# 3V8_Buck_Boost_Converter.net
KiCad netlist of a schematic drawn in Altium Designer
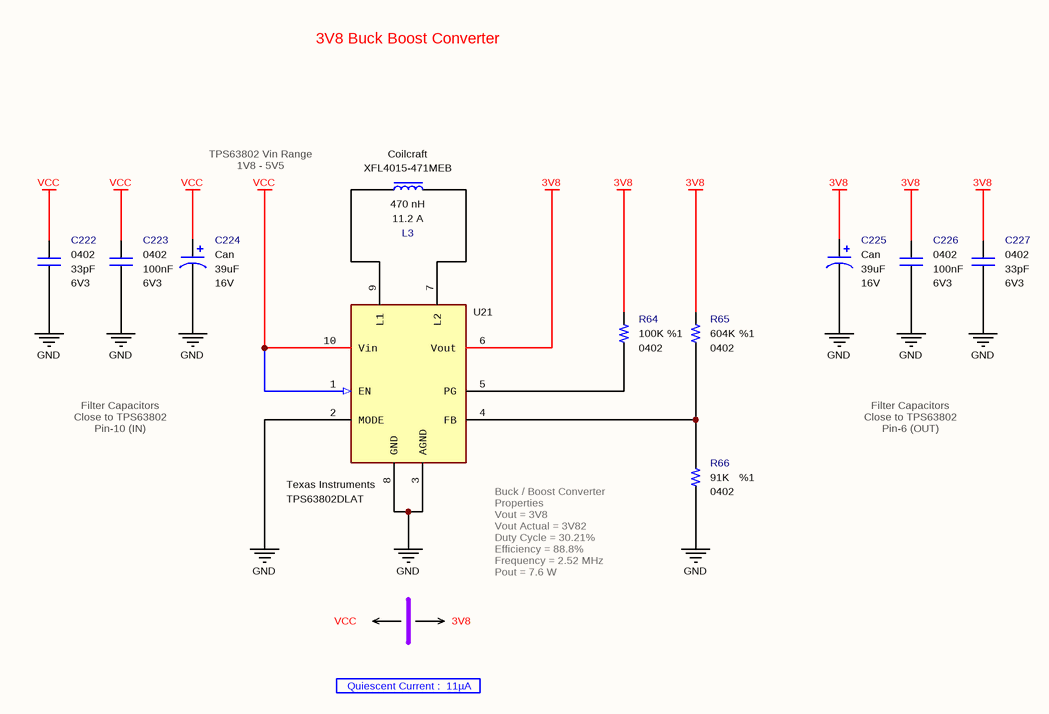
[diagram p0: 3V8 Buck Boost Converter.SchDoc]

(export (version "E")
  (design (tool "Eeschema 10.0.6"))
  (components
    (comp (ref "C222")
      (value "33pF")
      (footprint "CAPACITOR_0402")
      (description "Capacitor - 33pF [0402] (Ceramic)")
      (fields
        (field (name "TOLERANCE") "10%")
        (field (name "CASE") "0402")
        (field (name "VOLTAGE") "6V3")
        (field (name "MANUFACTURER PART NUMBER") "C0402C330J9RACAUTO")
      )
      (libsource (lib "Ovoo_Library") (part "Capacitor - 33pF [0402-6V3]"))
    )
    (comp (ref "C223")
      (value "100nF")
      (footprint "CAPACITOR_0402")
      (description "Capacitor - 100nF [0402-6V3] (Ceramic)")
      (fields
        (field (name "CASE") "0402")
        (field (name "TOLERANCE") "%10")
        (field (name "VOLTAGE") "6V3")
        (field (name "MANUFACTURER PART NUMBER") "04026D104KAT4A")
      )
      (libsource (lib "Ovoo_Library") (part "Capacitor - 100nF [0402-6V3]"))
    )
    (comp (ref "C224")
      (value "39uF")
      (footprint "CAPACITOR_CAN-B6")
      (description "Capacitor - 39uF 16V [Can] (Electrolytic)")
      (fields
        (field (name "TOLERANCE") "20%")
        (field (name "CASE") "Can")
        (field (name "VOLTAGE") "16V")
        (field (name "MANUFACTURER PART NUMBER") "16SVPC39MV")
      )
      (libsource (lib "Ovoo_Library") (part "Capacitor - 39uF [Can-16V]"))
    )
    (comp (ref "C225")
      (value "39uF")
      (footprint "CAPACITOR_CAN-B6")
      (description "Capacitor - 39uF 16V [Can] (Electrolytic)")
      (fields
        (field (name "TOLERANCE") "20%")
        (field (name "CASE") "Can")
        (field (name "VOLTAGE") "16V")
        (field (name "MANUFACTURER PART NUMBER") "16SVPC39MV")
      )
      (libsource (lib "Ovoo_Library") (part "Capacitor - 39uF [Can-16V]"))
    )
    (comp (ref "C226")
      (value "100nF")
      (footprint "CAPACITOR_0402")
      (description "Capacitor - 100nF [0402-6V3] (Ceramic)")
      (fields
        (field (name "CASE") "0402")
        (field (name "TOLERANCE") "%10")
        (field (name "VOLTAGE") "6V3")
        (field (name "MANUFACTURER PART NUMBER") "04026D104KAT4A")
      )
      (libsource (lib "Ovoo_Library") (part "Capacitor - 100nF [0402-6V3]"))
    )
    (comp (ref "C227")
      (value "33pF")
      (footprint "CAPACITOR_0402")
      (description "Capacitor - 33pF [0402] (Ceramic)")
      (fields
        (field (name "TOLERANCE") "10%")
        (field (name "CASE") "0402")
        (field (name "VOLTAGE") "6V3")
        (field (name "MANUFACTURER PART NUMBER") "C0402C330J9RACAUTO")
      )
      (libsource (lib "Ovoo_Library") (part "Capacitor - 33pF [0402-6V3]"))
    )
    (comp (ref "L3")
      (value "470 nH")
      (footprint "INDUCTOR_XFL4015")
      (description "Fixed Inductors 0.47uH 20% 11.2A 8.36mOhms AEC-Q200")
      (fields
        (field (name "TOLERANCE") "20%")
        (field (name "MAXIMUM DC CURRENT") "11.2 A")
        (field (name "MOUSER PART NUMBER") "994-XFL4015-471MEB")
        (field (name "MANUFACTURER PART NUMBER") "XFL4015-471MEB")
        (field (name "MANUFACTURER NAME") "Coilcraft")
      )
      (libsource (lib "Ovoo_Library") (part "Inductor - 470 nH [SMD]"))
    )
    (comp (ref "R64")
      (value "100K")
      (footprint "RESISTOR_0402")
      (description "Thick Film Resistors - SMD 1/16 W 100 Kohms 1%")
      (fields
        (field (name "TOLERANCE") "%1")
        (field (name "CASE") "0402")
        (field (name "MANUFACTURER PART NUMBER") "CRCW0402100KFKED")
        (field (name "MOUSER PART NUMBER") "71-CRCW0402-100K-E3")
      )
      (libsource (lib "Ovoo_Library") (part "Resistor - 100K"))
    )
    (comp (ref "R65")
      (value "604K")
      (footprint "RESISTOR_0402")
      (description "Thick Film Resistors - SMD 1/16 W 604 Kohms 1%")
      (fields
        (field (name "TOLERANCE") "%1")
        (field (name "CASE") "0402")
        (field (name "MANUFACTURER PART NUMBER") "CRCW0402604KFKED")
        (field (name "MOUSER PART NUMBER") "71-CRCW0402-604K-E3")
      )
      (libsource (lib "Ovoo_Library") (part "Resistor - 604K"))
    )
    (comp (ref "R66")
      (value "91K")
      (footprint "RESISTOR_0402")
      (description "Thick Film Resistors - SMD 1/16 W 91 Kohms 1%")
      (fields
        (field (name "TOLERANCE") "%1")
        (field (name "CASE") "0402")
        (field (name "MANUFACTURER PART NUMBER") "CRCW040291K0FKED")
        (field (name "MOUSER PART NUMBER") "71-CRCW040291K0FKED")
      )
      (libsource (lib "Ovoo_Library") (part "Resistor - 91K"))
    )
    (comp (ref "U21")
      (value "Buck-Boost Converter")
      (footprint "VSON-10")
      (fields
        (field (name "MOUSER PART NUMBER") "595-TPS63802DLAT")
        (field (name "MANUFACTURER PART NUMBER") "TPS63802DLAT")
        (field (name "MANUFACTURER NAME") "Texas Instruments")
      )
      (libsource (lib "Ovoo_Library") (part "IC - TPS63802DLAT"))
    )
  )
  (nets
    (net (code "1") (name "3V8") (class "Default")
      (node (ref "C225") (pin "1") (pinfunction "1_1") (pintype "passive"))
      (node (ref "C226") (pin "1") (pinfunction "1_1") (pintype "passive"))
      (node (ref "C227") (pin "2") (pinfunction "2_2") (pintype "passive"))
      (node (ref "R64") (pin "2") (pinfunction "2_2") (pintype "passive"))
      (node (ref "R65") (pin "2") (pinfunction "2_2") (pintype "passive"))
      (node (ref "U21") (pin "6") (pinfunction "Vout_6") (pintype "power_in"))
    )
    (net (code "2") (name "GND") (class "Default")
      (node (ref "C222") (pin "1") (pinfunction "1_1") (pintype "passive"))
      (node (ref "C223") (pin "2") (pinfunction "2_2") (pintype "passive"))
      (node (ref "C224") (pin "2") (pinfunction "2_2") (pintype "passive"))
      (node (ref "C225") (pin "2") (pinfunction "2_2") (pintype "passive"))
      (node (ref "C226") (pin "2") (pinfunction "2_2") (pintype "passive"))
      (node (ref "C227") (pin "1") (pinfunction "1_1") (pintype "passive"))
      (node (ref "R66") (pin "1") (pinfunction "1_1") (pintype "passive"))
      (node (ref "U21") (pin "2") (pinfunction "MODE_2") (pintype "passive"))
      (node (ref "U21") (pin "3") (pinfunction "AGND_3") (pintype "power_in"))
      (node (ref "U21") (pin "8") (pinfunction "GND_8") (pintype "power_in"))
    )
    (net (code "3") (name "Net-(U21-FB)") (class "Default")
      (node (ref "R65") (pin "1") (pinfunction "1_1") (pintype "passive"))
      (node (ref "R66") (pin "2") (pinfunction "2_2") (pintype "passive"))
      (node (ref "U21") (pin "4") (pinfunction "FB_4") (pintype "passive"))
    )
    (net (code "4") (name "Net-(U21-L1)") (class "Default")
      (node (ref "L3") (pin "1") (pinfunction "1_1") (pintype "passive"))
      (node (ref "U21") (pin "9") (pinfunction "L1_9") (pintype "passive"))
    )
    (net (code "5") (name "Net-(U21-L2)") (class "Default")
      (node (ref "L3") (pin "2") (pinfunction "2_2") (pintype "passive"))
      (node (ref "U21") (pin "7") (pinfunction "L2_7") (pintype "passive"))
    )
    (net (code "6") (name "Net-(U21-PG)") (class "Default")
      (node (ref "R64") (pin "1") (pinfunction "1_1") (pintype "passive"))
      (node (ref "U21") (pin "5") (pinfunction "PG_5") (pintype "passive"))
    )
    (net (code "7") (name "VCC") (class "Default")
      (node (ref "C222") (pin "2") (pinfunction "2_2") (pintype "passive"))
      (node (ref "C223") (pin "1") (pinfunction "1_1") (pintype "passive"))
      (node (ref "C224") (pin "1") (pinfunction "1_1") (pintype "passive"))
      (node (ref "U21") (pin "1") (pinfunction "EN_1") (pintype "input"))
      (node (ref "U21") (pin "10") (pinfunction "Vin_10") (pintype "power_in"))
    )
  )
)
